# ASIC.net
KiCad netlist of a schematic drawn in Altium Designer
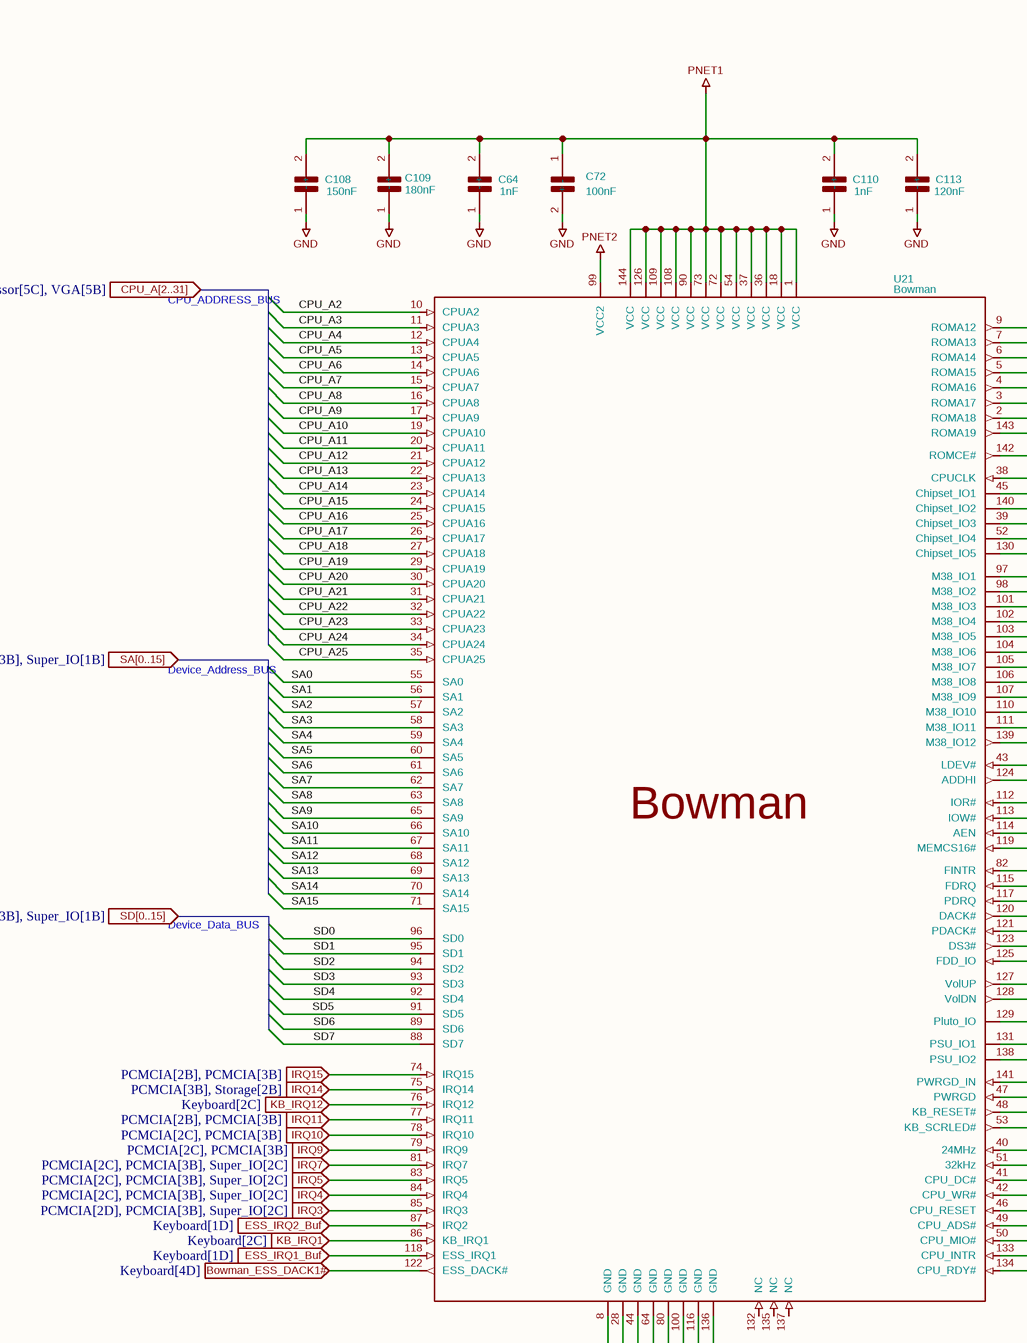
[diagram p0: ASIC.SchDoc, top left]
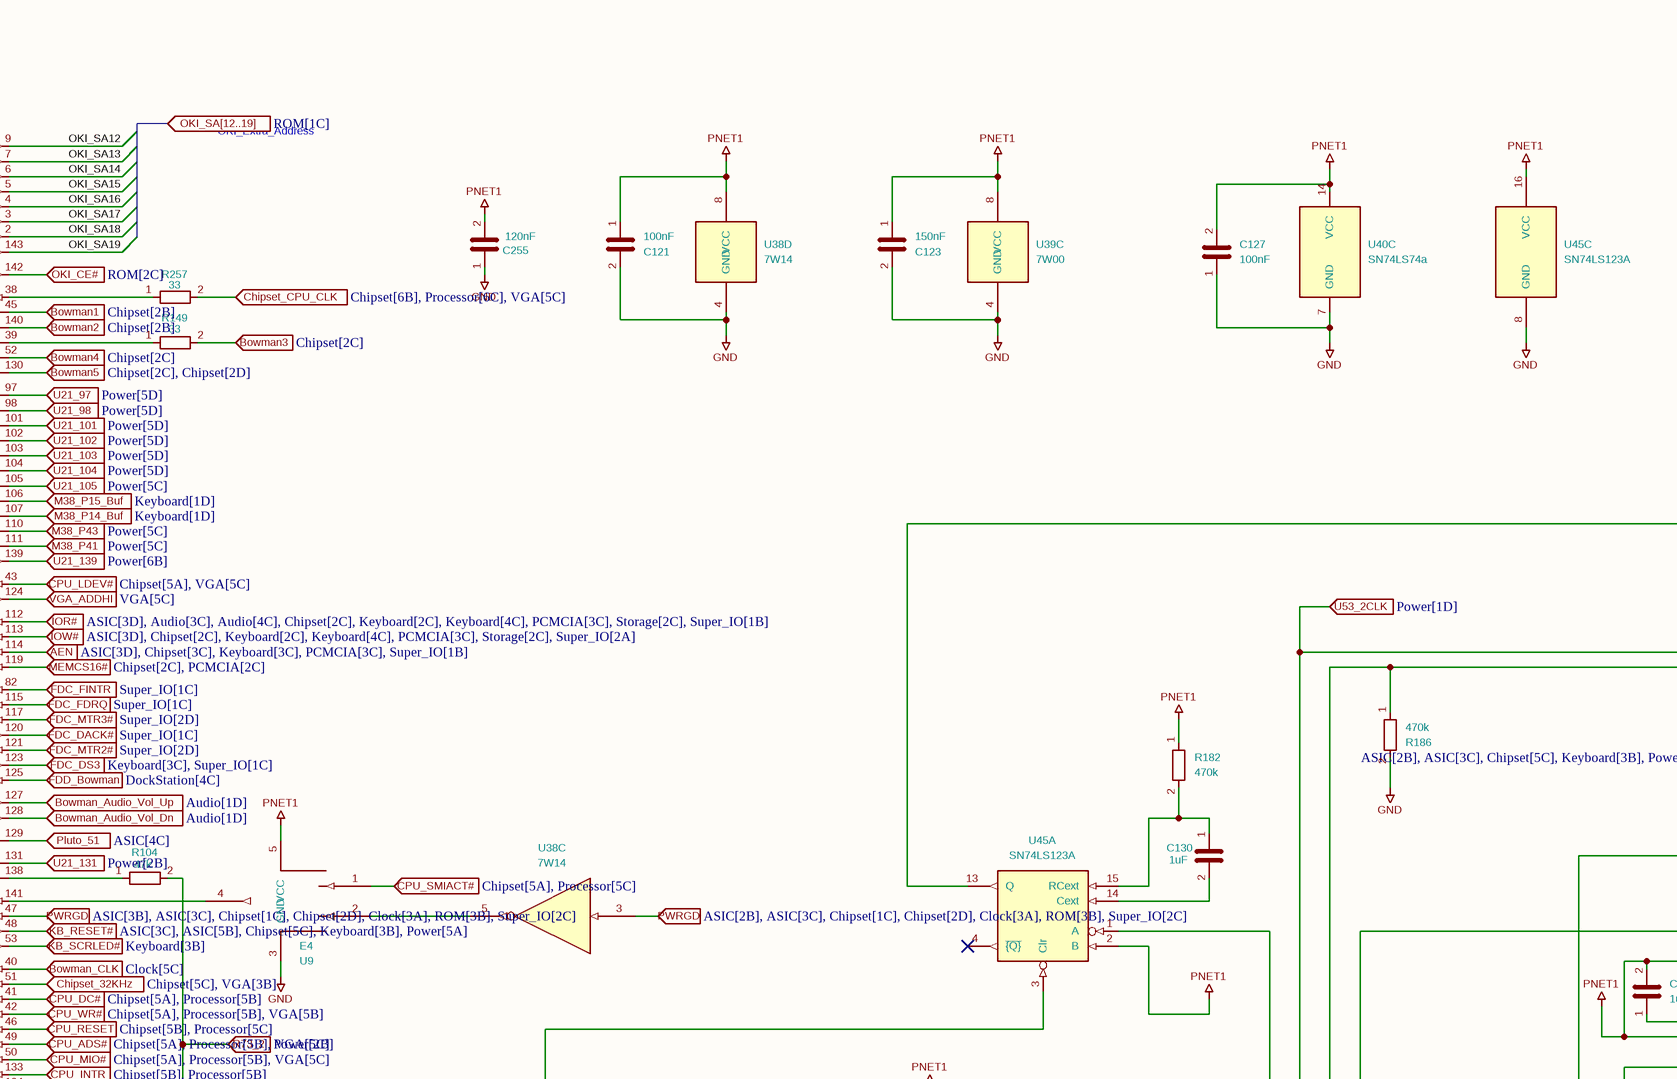
[diagram p1: ASIC.SchDoc, top middle]
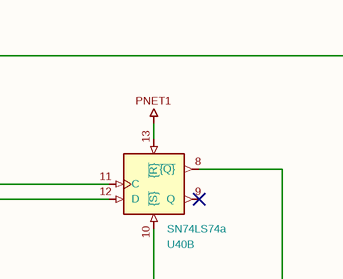
[diagram p2: ASIC.SchDoc, top right]
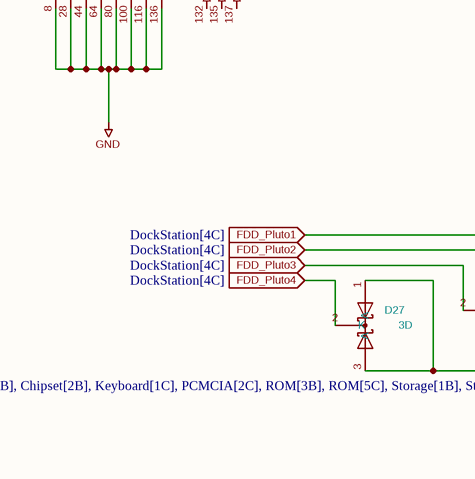
[diagram p3: ASIC.SchDoc, bottom left]
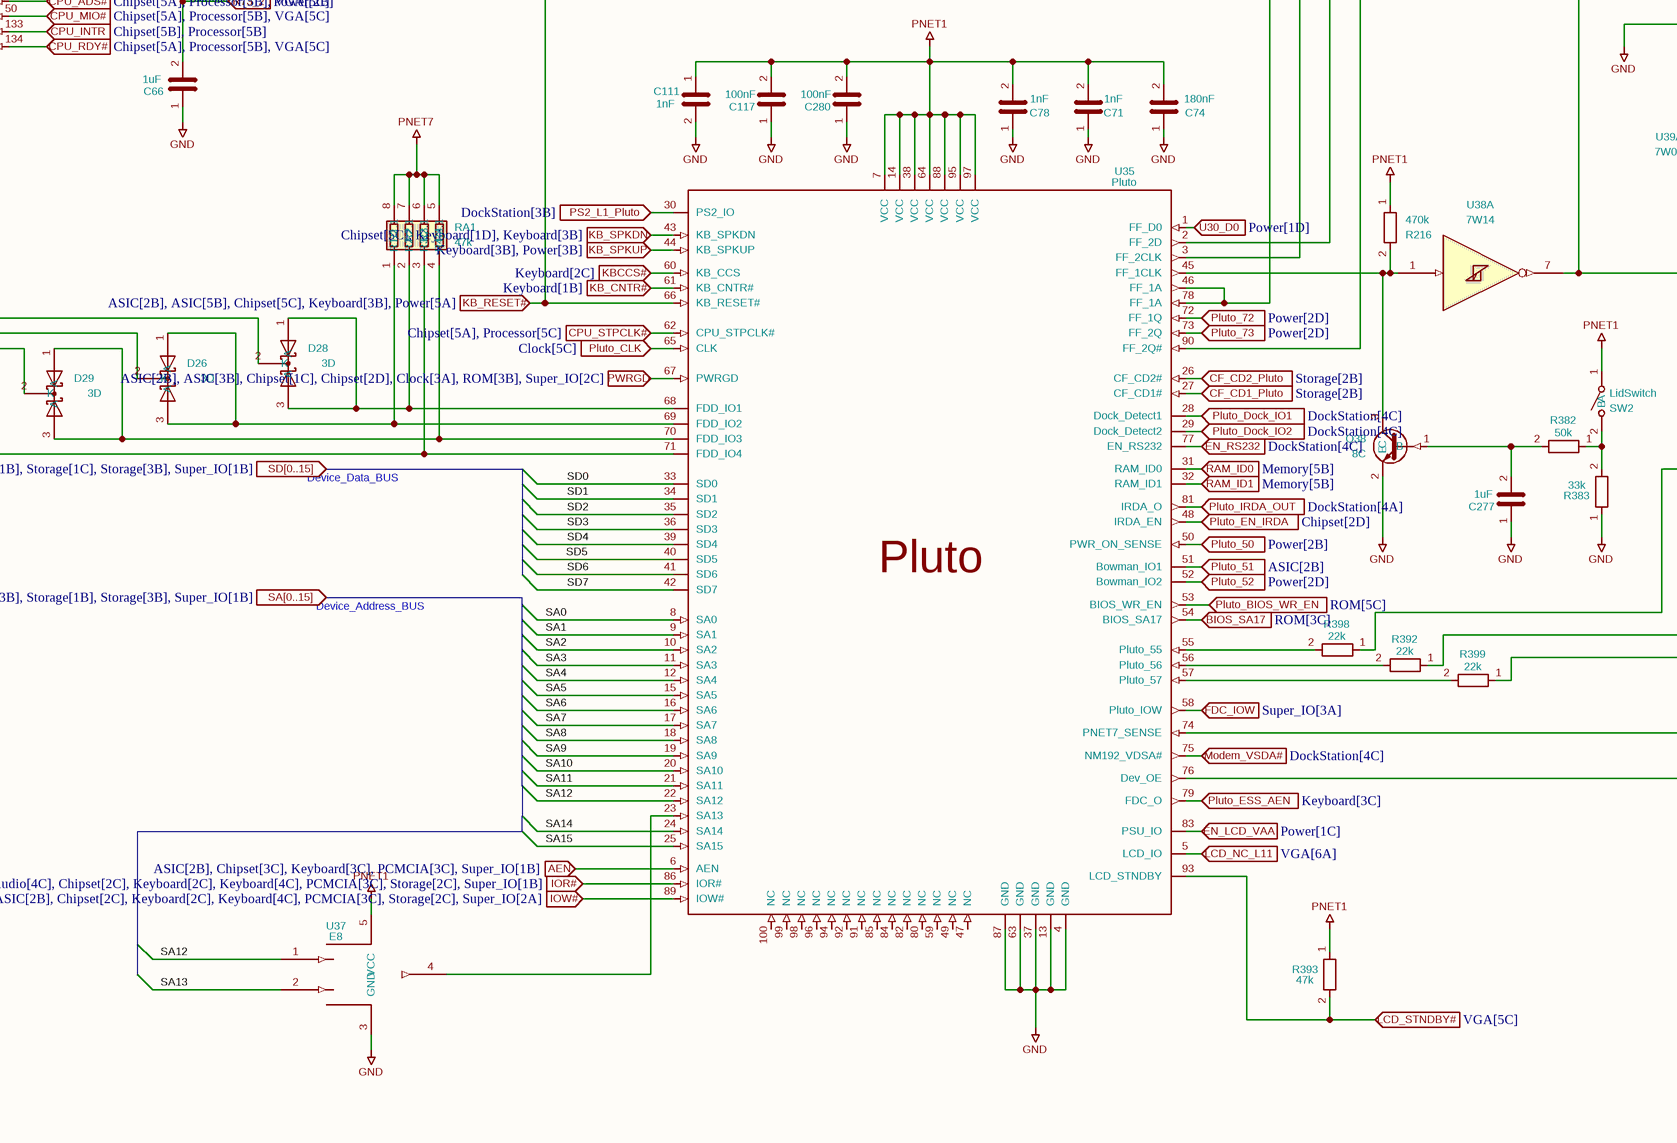
[diagram p4: ASIC.SchDoc, bottom middle]
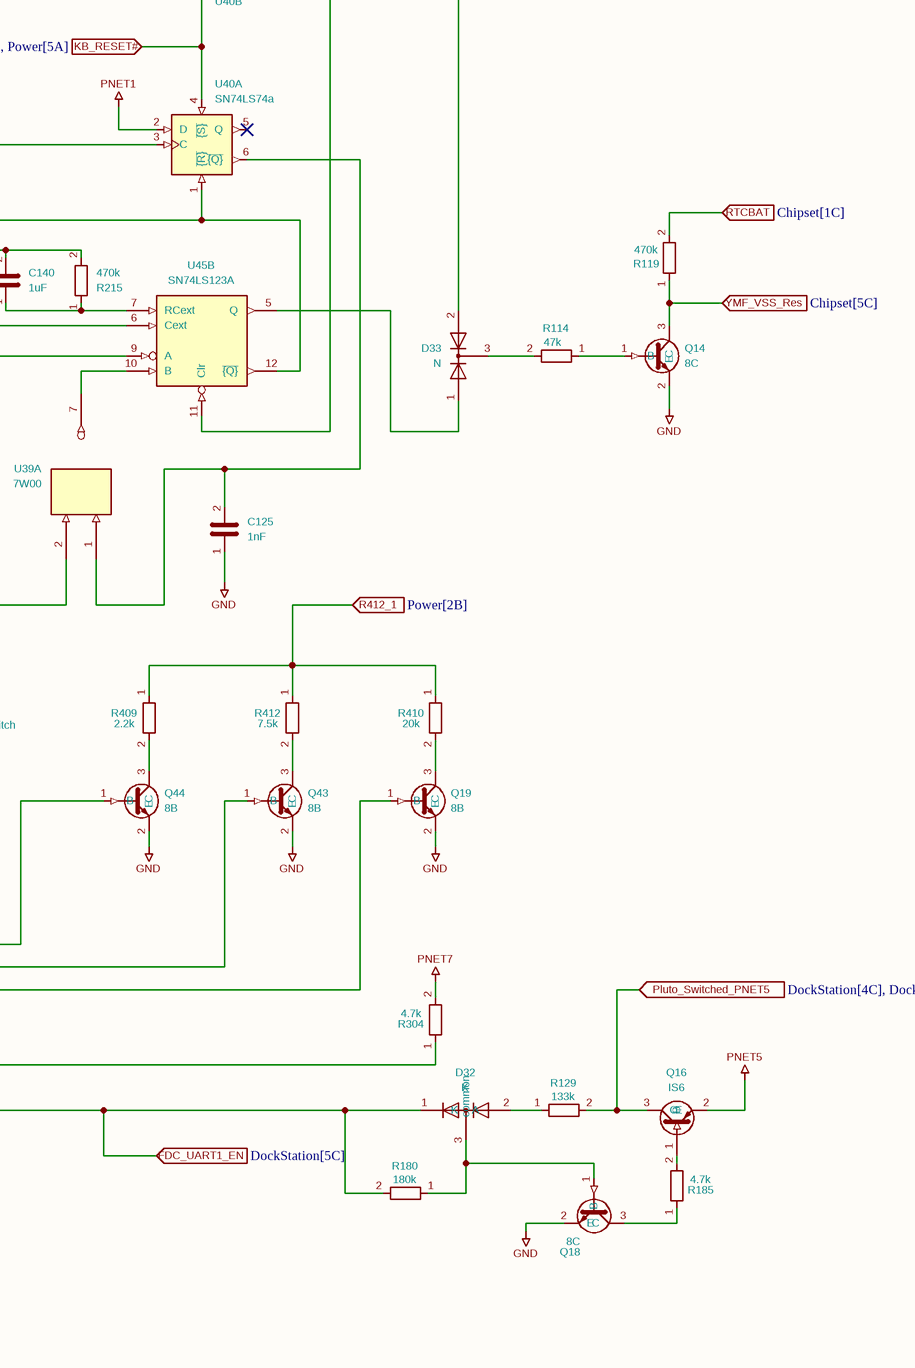
[diagram p5: ASIC.SchDoc, bottom right]

(export (version "E")
  (design (tool "Eeschema 10.0.6"))
  (components
    (comp (ref "C64") (value "1nF") (footprint "C_0402_1005Metric") (libsource (lib "") (part "C_1")))
    (comp (ref "C66") (value "1uF") (footprint "C_0603_1608Metric") (libsource (lib "Device") (part "C")))
    (comp (ref "C71") (value "1nF") (footprint "C_0402_1005Metric") (libsource (lib "Device") (part "C")))
    (comp (ref "C72")
      (value "100nF")
      (footprint "C_0402_1005Metric")
      (libsource (lib "PCM_Elektuur") (part "C"))
    )
    (comp (ref "C74") (value "180nF") (footprint "C_0402_1005Metric") (libsource (lib "Device") (part "C")))
    (comp (ref "C78") (value "1nF") (footprint "C_0402_1005Metric") (libsource (lib "Device") (part "C")))
    (comp (ref "C108") (value "150nF") (footprint "C_0402_1005Metric") (libsource (lib "") (part "C_1")))
    (comp (ref "C109") (value "180nF") (footprint "C_0402_1005Metric") (libsource (lib "") (part "C_1")))
    (comp (ref "C110") (value "1nF") (footprint "C_0402_1005Metric") (libsource (lib "") (part "C_1")))
    (comp (ref "C111") (value "1nF") (footprint "C_0402_1005Metric") (libsource (lib "Device") (part "C")))
    (comp (ref "C113") (value "120nF") (footprint "C_0402_1005Metric") (libsource (lib "") (part "C_1")))
    (comp (ref "C117") (value "100nF") (footprint "C_0402_1005Metric") (libsource (lib "Device") (part "C")))
    (comp (ref "C121") (value "100nF") (footprint "C_0402_1005Metric") (libsource (lib "Device") (part "C")))
    (comp (ref "C123") (value "150nF") (footprint "C_0402_1005Metric") (libsource (lib "Device") (part "C")))
    (comp (ref "C125") (value "1nF") (footprint "C_0402_1005Metric") (libsource (lib "Device") (part "C")))
    (comp (ref "C127") (value "100nF") (footprint "C_0402_1005Metric") (libsource (lib "Device") (part "C")))
    (comp (ref "C130") (value "1uF") (footprint "C_0603_1608Metric") (libsource (lib "Device") (part "C")))
    (comp (ref "C140") (value "1uF") (footprint "C_0603_1608Metric") (libsource (lib "Device") (part "C")))
    (comp (ref "C255") (value "120nF") (footprint "C_0402_1005Metric") (libsource (lib "Device") (part "C")))
    (comp (ref "C277") (value "1uF") (footprint "C_0603_1608Metric") (libsource (lib "Device") (part "C")))
    (comp (ref "C280") (value "100nF") (footprint "C_0402_1005Metric") (libsource (lib "Device") (part "C")))
    (comp (ref "D26")
      (value "3D")
      (footprint "3D")
      (libsource (lib "Device") (part "D_Schottky_Dual_CommonCathode_AKA"))
    )
    (comp (ref "D27")
      (value "3D")
      (footprint "3D")
      (libsource (lib "Device") (part "D_Schottky_Dual_CommonCathode_AKA"))
    )
    (comp (ref "D28")
      (value "3D")
      (footprint "3D")
      (libsource (lib "Device") (part "D_Schottky_Dual_CommonCathode_AKA"))
    )
    (comp (ref "D29")
      (value "3D")
      (footprint "3D")
      (libsource (lib "Device") (part "D_Schottky_Dual_CommonCathode_AKA"))
    )
    (comp (ref "D32")
      (value "K")
      (footprint "SOT-416L")
      (libsource (lib "Device") (part "D_Dual_Series_KAC"))
    )
    (comp (ref "D33") (value "N") (footprint "SOT-416") (libsource (lib "PC110") (part "3D_Diode")))
    (comp (ref "Q14") (value "8C") (footprint "SOT-416") (libsource (lib "Transistor_BJT") (part "MMBTA44")))
    (comp (ref "Q16")
      (value "IS6")
      (footprint "TSOT-23")
      (libsource (lib "PCM_Transistor_BJT_AKL") (part "Q_PNP_Generic_BEC"))
    )
    (comp (ref "Q18") (value "8C") (footprint "SOT-416") (libsource (lib "Transistor_BJT") (part "MMBTA44")))
    (comp (ref "Q19") (value "8B") (footprint "SOT-416") (libsource (lib "Transistor_BJT") (part "MMBTA44")))
    (comp (ref "Q38") (value "8C") (footprint "SOT-416") (libsource (lib "Transistor_BJT") (part "MMBTA44")))
    (comp (ref "Q43") (value "8B") (footprint "SOT-523") (libsource (lib "Transistor_BJT") (part "MMBTA44")))
    (comp (ref "Q44") (value "8B") (footprint "SOT-523") (libsource (lib "Transistor_BJT") (part "MMBTA44")))
    (comp (ref "R104") (value "47k") (footprint "R_0402_1005Metric") (libsource (lib "") (part "R_1")))
    (comp (ref "R114") (value "47k") (footprint "R_0402_1005Metric") (libsource (lib "") (part "R_2")))
    (comp (ref "R119") (value "470k") (footprint "R_0402_1005Metric") (libsource (lib "") (part "R_1")))
    (comp (ref "R129") (value "133k") (footprint "R_0402_1005Metric") (libsource (lib "") (part "R_3")))
    (comp (ref "R149") (value "33") (footprint "R_0402_1005Metric") (libsource (lib "") (part "R_1")))
    (comp (ref "R180") (value "180k") (footprint "R_0402_1005Metric") (libsource (lib "") (part "R_2")))
    (comp (ref "R182") (value "470k") (footprint "R_0402_1005Metric") (libsource (lib "Device") (part "R")))
    (comp (ref "R185") (value "4.7k") (footprint "R_0402_1005Metric") (libsource (lib "") (part "R_3")))
    (comp (ref "R186") (value "470k") (footprint "R_0402_1005Metric") (libsource (lib "") (part "R_2")))
    (comp (ref "R215") (value "470k") (footprint "R_0402_1005Metric") (libsource (lib "") (part "R_1")))
    (comp (ref "R216") (value "470k") (footprint "R_0402_1005Metric") (libsource (lib "") (part "R_2")))
    (comp (ref "R257") (value "33") (footprint "R_0402_1005Metric") (libsource (lib "") (part "R_1")))
    (comp (ref "R304") (value "4.7k") (footprint "R_0402_1005Metric") (libsource (lib "") (part "R_1")))
    (comp (ref "R382") (value "50k") (footprint "R_0402_1005Metric") (libsource (lib "") (part "R_2")))
    (comp (ref "R383") (value "33k") (footprint "R_0402_1005Metric") (libsource (lib "") (part "R_1")))
    (comp (ref "R392") (value "22k") (footprint "R_0402_1005Metric") (libsource (lib "") (part "R_2")))
    (comp (ref "R393") (value "47k") (footprint "R_0402_1005Metric") (libsource (lib "Device") (part "R")))
    (comp (ref "R398") (value "22k") (footprint "R_0402_1005Metric") (libsource (lib "") (part "R_2")))
    (comp (ref "R399") (value "22k") (footprint "R_0402_1005Metric") (libsource (lib "") (part "R_2")))
    (comp (ref "R409") (value "2.2k") (footprint "R_0402_1005Metric") (libsource (lib "Device") (part "R")))
    (comp (ref "R410") (value "20k") (footprint "R_0402_1005Metric") (libsource (lib "Device") (part "R")))
    (comp (ref "R412") (value "7.5k") (footprint "R_0402_1005Metric") (libsource (lib "Device") (part "R")))
    (comp (ref "RA1") (value "47k") (footprint "R-array") (libsource (lib "Device") (part "R_Pack04")))
    (comp (ref "SW2") (value "LidSwitch") (footprint "LidSwitch") (libsource (lib "Switch") (part "SW_SPST")))
    (comp (ref "U9") (value "E4") (footprint "SOT-353") (libsource (lib "74xGxx") (part "74AHC1G32")))
    (comp (ref "U21") (value "Bowman") (footprint "Bowman") (libsource (lib "PC110") (part "Bowman")))
    (comp (ref "U35") (value "Pluto") (footprint "Pluto") (libsource (lib "PC110") (part "Pluto")))
    (comp (ref "U37") (value "E8") (footprint "SOT-353") (libsource (lib "74xGxx") (part "74AHC1G86")))
    (comp (ref "U38") (value "7W14") (footprint "sso-8") (libsource (lib "") (part "74LVC3G14_1")))
    (comp (ref "U39") (value "7W00") (footprint "sso-8") (libsource (lib "74xGxx") (part "74AHC2G00")))
    (comp (ref "U40")
      (value "SN74LS74a")
      (footprint "TSSOP-14_4.4x5mm_P0.65mm")
      (libsource (lib "74xx") (part "74HC74"))
    )
    (comp (ref "U45")
      (value "SN74LS123A")
      (footprint "TSSOP-16_4.4x5mm_P0.65mm")
      (libsource (lib "74xx") (part "74HC123"))
    )
  )
  (nets
    (net (code "15") (name "/AEN") (class "Default")
      (node (ref "U21") (pin "114") (pinfunction "AEN_114") (pintype "input"))
      (node (ref "U35") (pin "6") (pinfunction "AEN_6") (pintype "input"))
    )
    (net (code "16") (name "/BIOS_SA17") (class "Default")
      (node (ref "U35") (pin "54") (pinfunction "BIOS_SA17_54") (pintype "output"))
    )
    (net (code "17") (name "/Bowman1") (class "Default")
      (node (ref "U21") (pin "45") (pinfunction "Chipset_IO1_45") (pintype "bidirectional"))
    )
    (net (code "18") (name "/Bowman2") (class "Default")
      (node (ref "U21") (pin "140") (pinfunction "Chipset_IO2_140") (pintype "bidirectional"))
    )
    (net (code "19") (name "/Bowman3") (class "Default")
      (node (ref "R149") (pin "2") (pinfunction "2_2") (pintype "passive"))
    )
    (net (code "20") (name "/Bowman4") (class "Default")
      (node (ref "U21") (pin "52") (pinfunction "Chipset_IO4_52") (pintype "bidirectional"))
    )
    (net (code "21") (name "/Bowman5") (class "Default")
      (node (ref "U21") (pin "130") (pinfunction "Chipset_IO5_130") (pintype "bidirectional"))
    )
    (net (code "22") (name "/Bowman_Audio_Vol_Dn") (class "Default")
      (node (ref "U21") (pin "128") (pinfunction "VolDN_128") (pintype "output"))
    )
    (net (code "23") (name "/Bowman_Audio_Vol_Up") (class "Default")
      (node (ref "U21") (pin "127") (pinfunction "VolUP_127") (pintype "output"))
    )
    (net (code "24") (name "/Bowman_CLK") (class "Default")
      (node (ref "U21") (pin "40") (pinfunction "24MHz_40") (pintype "input"))
    )
    (net (code "25") (name "/Bowman_ESS_DACK1#") (class "Default")
      (node (ref "U21") (pin "122") (pinfunction "ESS_DACK#_122") (pintype "output"))
    )
    (net (code "26") (name "/CF_CD1_Pluto") (class "Default")
      (node (ref "U35") (pin "27") (pinfunction "CF_CD1#_27") (pintype "input"))
    )
    (net (code "27") (name "/CF_CD2_Pluto") (class "Default")
      (node (ref "U35") (pin "26") (pinfunction "CF_CD2#_26") (pintype "input"))
    )
    (net (code "28") (name "/CPU_A2") (class "Default")
      (node (ref "U21") (pin "10") (pinfunction "CPUA2_10") (pintype "input"))
    )
    (net (code "29") (name "/CPU_A3") (class "Default")
      (node (ref "U21") (pin "11") (pinfunction "CPUA3_11") (pintype "input"))
    )
    (net (code "30") (name "/CPU_A4") (class "Default")
      (node (ref "U21") (pin "12") (pinfunction "CPUA4_12") (pintype "input"))
    )
    (net (code "31") (name "/CPU_A5") (class "Default")
      (node (ref "U21") (pin "13") (pinfunction "CPUA5_13") (pintype "input"))
    )
    (net (code "32") (name "/CPU_A6") (class "Default")
      (node (ref "U21") (pin "14") (pinfunction "CPUA6_14") (pintype "input"))
    )
    (net (code "33") (name "/CPU_A7") (class "Default")
      (node (ref "U21") (pin "15") (pinfunction "CPUA7_15") (pintype "input"))
    )
    (net (code "34") (name "/CPU_A8") (class "Default")
      (node (ref "U21") (pin "16") (pinfunction "CPUA8_16") (pintype "input"))
    )
    (net (code "35") (name "/CPU_A9") (class "Default")
      (node (ref "U21") (pin "17") (pinfunction "CPUA9_17") (pintype "input"))
    )
    (net (code "36") (name "/CPU_A10") (class "Default")
      (node (ref "U21") (pin "19") (pinfunction "CPUA10_19") (pintype "input"))
    )
    (net (code "37") (name "/CPU_A11") (class "Default")
      (node (ref "U21") (pin "20") (pinfunction "CPUA11_20") (pintype "input"))
    )
    (net (code "38") (name "/CPU_A12") (class "Default")
      (node (ref "U21") (pin "21") (pinfunction "CPUA12_21") (pintype "input"))
    )
    (net (code "39") (name "/CPU_A13") (class "Default")
      (node (ref "U21") (pin "22") (pinfunction "CPUA13_22") (pintype "input"))
    )
    (net (code "40") (name "/CPU_A14") (class "Default")
      (node (ref "U21") (pin "23") (pinfunction "CPUA14_23") (pintype "input"))
    )
    (net (code "41") (name "/CPU_A15") (class "Default")
      (node (ref "U21") (pin "24") (pinfunction "CPUA15_24") (pintype "input"))
    )
    (net (code "42") (name "/CPU_A16") (class "Default")
      (node (ref "U21") (pin "25") (pinfunction "CPUA16_25") (pintype "input"))
    )
    (net (code "43") (name "/CPU_A17") (class "Default")
      (node (ref "U21") (pin "26") (pinfunction "CPUA17_26") (pintype "input"))
    )
    (net (code "44") (name "/CPU_A18") (class "Default")
      (node (ref "U21") (pin "27") (pinfunction "CPUA18_27") (pintype "input"))
    )
    (net (code "45") (name "/CPU_A19") (class "Default")
      (node (ref "U21") (pin "29") (pinfunction "CPUA19_29") (pintype "input"))
    )
    (net (code "46") (name "/CPU_A20") (class "Default")
      (node (ref "U21") (pin "30") (pinfunction "CPUA20_30") (pintype "input"))
    )
    (net (code "47") (name "/CPU_A21") (class "Default")
      (node (ref "U21") (pin "31") (pinfunction "CPUA21_31") (pintype "input"))
    )
    (net (code "48") (name "/CPU_A22") (class "Default")
      (node (ref "U21") (pin "32") (pinfunction "CPUA22_32") (pintype "input"))
    )
    (net (code "49") (name "/CPU_A23") (class "Default")
      (node (ref "U21") (pin "33") (pinfunction "CPUA23_33") (pintype "input"))
    )
    (net (code "50") (name "/CPU_A24") (class "Default")
      (node (ref "U21") (pin "34") (pinfunction "CPUA24_34") (pintype "input"))
    )
    (net (code "51") (name "/CPU_A25") (class "Default")
      (node (ref "U21") (pin "35") (pinfunction "CPUA25_35") (pintype "input"))
    )
    (net (code "52") (name "/CPU_ADS#") (class "Default")
      (node (ref "U21") (pin "49") (pinfunction "CPU_ADS#_49") (pintype "input"))
    )
    (net (code "54") (name "/CPU_DC#") (class "Default")
      (node (ref "U21") (pin "41") (pinfunction "CPU_DC#_41") (pintype "input"))
    )
    (net (code "55") (name "/CPU_INTR") (class "Default")
      (node (ref "U21") (pin "133") (pinfunction "CPU_INTR_133") (pintype "input"))
    )
    (net (code "56") (name "/CPU_LDEV#") (class "Default")
      (node (ref "U21") (pin "43") (pinfunction "LDEV#_43") (pintype "input"))
    )
    (net (code "57") (name "/CPU_MIO#") (class "Default")
      (node (ref "U21") (pin "50") (pinfunction "CPU_MIO#_50") (pintype "input"))
    )
    (net (code "58") (name "/CPU_RDY#") (class "Default")
      (node (ref "U21") (pin "134") (pinfunction "CPU_RDY#_134") (pintype "input"))
    )
    (net (code "59") (name "/CPU_RESET") (class "Default")
      (node (ref "U21") (pin "46") (pinfunction "CPU_RESET_46") (pintype "input"))
    )
    (net (code "60") (name "/CPU_SMIACT#") (class "Default")
      (node (ref "U9") (pin "1") (pinfunction "1_1") (pintype "input"))
    )
    (net (code "61") (name "/CPU_STPCLK#") (class "Default")
      (node (ref "U35") (pin "62") (pinfunction "CPU_STPCLK#_62") (pintype "input"))
    )
    (net (code "62") (name "/CPU_WR#") (class "Default")
      (node (ref "U21") (pin "42") (pinfunction "CPU_WR#_42") (pintype "input"))
    )
    (net (code "63") (name "/Chipset_32KHz") (class "Default")
      (node (ref "U21") (pin "51") (pinfunction "32kHz_51") (pintype "input"))
    )
    (net (code "64") (name "/Chipset_CPU_CLK") (class "Default")
      (node (ref "R257") (pin "2") (pinfunction "2_2") (pintype "passive"))
    )
    (net (code "65") (name "/EN_LCD_VAA") (class "Default")
      (node (ref "U35") (pin "83") (pinfunction "PSU_IO_83") (pintype "bidirectional"))
    )
    (net (code "66") (name "/EN_RS232") (class "Default")
      (node (ref "U35") (pin "77") (pinfunction "EN_RS232_77") (pintype "bidirectional"))
    )
    (net (code "67") (name "/ESS_IRQ1_Buf") (class "Default")
      (node (ref "U21") (pin "118") (pinfunction "ESS_IRQ1_118") (pintype "input"))
    )
    (net (code "68") (name "/ESS_IRQ2_Buf") (class "Default")
      (node (ref "U21") (pin "87") (pinfunction "IRQ2_87") (pintype "input"))
    )
    (net (code "69") (name "/FDC_DACK#") (class "Default")
      (node (ref "U21") (pin "120") (pinfunction "DACK#_120") (pintype "output"))
    )
    (net (code "70") (name "/FDC_DS3") (class "Default")
      (node (ref "U21") (pin "123") (pinfunction "DS3#_123") (pintype "output"))
    )
    (net (code "71") (name "/FDC_FDRQ") (class "Default")
      (node (ref "U21") (pin "115") (pinfunction "FDRQ_115") (pintype "input"))
    )
    (net (code "72") (name "/FDC_FINTR") (class "Default")
      (node (ref "U21") (pin "82") (pinfunction "FINTR_82") (pintype "input"))
    )
    (net (code "73") (name "/FDC_IOW") (class "Default")
      (node (ref "U35") (pin "58") (pinfunction "Pluto_IOW_58") (pintype "output"))
    )
    (net (code "74") (name "/FDC_MTR2#") (class "Default")
      (node (ref "U21") (pin "121") (pinfunction "PDACK#_121") (pintype "input"))
    )
    (net (code "75") (name "/FDC_MTR3#") (class "Default")
      (node (ref "U21") (pin "117") (pinfunction "PDRQ_117") (pintype "input"))
    )
    (net (code "76") (name "/FDC_UART1_EN") (class "Default")
      (node (ref "D32") (pin "1") (pinfunction "K_1") (pintype "passive"))
      (node (ref "R180") (pin "2") (pinfunction "2_2") (pintype "passive"))
      (node (ref "U35") (pin "76") (pinfunction "Dev_OE_76") (pintype "output"))
    )
    (net (code "77") (name "/FDD_Bowman") (class "Default")
      (node (ref "U21") (pin "125") (pinfunction "FDD_IO_125") (pintype "input"))
    )
    (net (code "78") (name "/FDD_Pluto1") (class "Default")
      (node (ref "D28") (pin "2") (pinfunction "K_2") (pintype "passive"))
    )
    (net (code "79") (name "/FDD_Pluto2") (class "Default")
      (node (ref "D26") (pin "2") (pinfunction "K_2") (pintype "passive"))
    )
    (net (code "80") (name "/FDD_Pluto3") (class "Default")
      (node (ref "D29") (pin "2") (pinfunction "K_2") (pintype "passive"))
    )
    (net (code "81") (name "/FDD_Pluto4") (class "Default")
      (node (ref "D27") (pin "2") (pinfunction "K_2") (pintype "passive"))
    )
    (net (code "82") (name "/IOR#") (class "Default")
      (node (ref "U21") (pin "112") (pinfunction "IOR#_112") (pintype "input"))
      (node (ref "U35") (pin "86") (pinfunction "IOR#_86") (pintype "input"))
    )
    (net (code "83") (name "/IOW#") (class "Default")
      (node (ref "U21") (pin "113") (pinfunction "IOW#_113") (pintype "input"))
      (node (ref "U35") (pin "89") (pinfunction "IOW#_89") (pintype "input"))
    )
    (net (code "84") (name "/IRQ3") (class "Default")
      (node (ref "U21") (pin "85") (pinfunction "IRQ3_85") (pintype "input"))
    )
    (net (code "85") (name "/IRQ4") (class "Default")
      (node (ref "U21") (pin "84") (pinfunction "IRQ4_84") (pintype "input"))
    )
    (net (code "86") (name "/IRQ5") (class "Default")
      (node (ref "U21") (pin "83") (pinfunction "IRQ5_83") (pintype "input"))
    )
    (net (code "87") (name "/IRQ7") (class "Default")
      (node (ref "U21") (pin "81") (pinfunction "IRQ7_81") (pintype "input"))
    )
    (net (code "88") (name "/IRQ9") (class "Default")
      (node (ref "U21") (pin "79") (pinfunction "IRQ9_79") (pintype "input"))
    )
    (net (code "89") (name "/IRQ10") (class "Default")
      (node (ref "U21") (pin "78") (pinfunction "IRQ10_78") (pintype "input"))
    )
    (net (code "90") (name "/IRQ11") (class "Default")
      (node (ref "U21") (pin "77") (pinfunction "IRQ11_77") (pintype "input"))
    )
    (net (code "91") (name "/IRQ14") (class "Default")
      (node (ref "U21") (pin "75") (pinfunction "IRQ14_75") (pintype "input"))
    )
    (net (code "92") (name "/IRQ15") (class "Default")
      (node (ref "U21") (pin "74") (pinfunction "IRQ15_74") (pintype "input"))
    )
    (net (code "93") (name "/KBCCS#") (class "Default")
      (node (ref "U35") (pin "60") (pinfunction "KB_CCS_60") (pintype "input"))
    )
    (net (code "94") (name "/KB_CNTR#") (class "Default")
      (node (ref "U35") (pin "61") (pinfunction "KB_CNTR#_61") (pintype "input"))
    )
    (net (code "95") (name "/KB_IRQ1") (class "Default")
      (node (ref "U21") (pin "86") (pinfunction "KB_IRQ1_86") (pintype "input"))
    )
    (net (code "96") (name "/KB_IRQ12") (class "Default")
      (node (ref "U21") (pin "76") (pinfunction "IRQ12_76") (pintype "input"))
    )
    (net (code "97") (name "/KB_RESET#") (class "Default")
      (node (ref "U21") (pin "48") (pinfunction "KB_RESET#_48") (pintype "output"))
      (node (ref "U35") (pin "66") (pinfunction "KB_RESET#_66") (pintype "input"))
      (node (ref "U40") (pin "10") (pinfunction "~{{S}}_10") (pintype "input"))
      (node (ref "U40") (pin "4") (pinfunction "~{{S}}_4") (pintype "input"))
      (node (ref "U45") (pin "3") (pinfunction "Clr_3") (pintype "input"))
    )
    (net (code "98") (name "/KB_SCRLED#") (class "Default")
      (node (ref "U21") (pin "53") (pinfunction "KB_SCRLED#_53") (pintype "output"))
    )
    (net (code "99") (name "/KB_SPKDN") (class "Default")
      (node (ref "U35") (pin "43") (pinfunction "KB_SPKDN_43") (pintype "input"))
    )
    (net (code "100") (name "/KB_SPKUP") (class "Default")
      (node (ref "U35") (pin "44") (pinfunction "KB_SPKUP_44") (pintype "input"))
    )
    (net (code "101") (name "/LCD_NC_L11") (class "Default")
      (node (ref "U35") (pin "5") (pinfunction "LCD_IO_5") (pintype "bidirectional"))
    )
    (net (code "102") (name "/LCD_STNDBY#") (class "Default")
      (node (ref "R393") (pin "2") (pinfunction "2_2") (pintype "passive"))
      (node (ref "U35") (pin "93") (pinfunction "LCD_STNDBY_93") (pintype "bidirectional"))
    )
    (net (code "103") (name "/M38_P14_Buf") (class "Default")
      (node (ref "U21") (pin "107") (pinfunction "M38_IO9_107") (pintype "bidirectional"))
    )
    (net (code "104") (name "/M38_P15_Buf") (class "Default")
      (node (ref "U21") (pin "106") (pinfunction "M38_IO8_106") (pintype "bidirectional"))
    )
    (net (code "105") (name "/M38_P41") (class "Default")
      (node (ref "U21") (pin "111") (pinfunction "M38_IO11_111") (pintype "bidirectional"))
    )
    (net (code "106") (name "/M38_P43") (class "Default")
      (node (ref "U21") (pin "110") (pinfunction "M38_IO10_110") (pintype "bidirectional"))
    )
    (net (code "107") (name "/MEMCS16#") (class "Default")
      (node (ref "U21") (pin "119") (pinfunction "MEMCS16#_119") (pintype "input"))
    )
    (net (code "108") (name "/Modem_VSDA#") (class "Default")
      (node (ref "U35") (pin "75") (pinfunction "NM192_VDSA#_75") (pintype "output"))
    )
    (net (code "109") (name "/OKI_CE#") (class "Default")
      (node (ref "U21") (pin "142") (pinfunction "ROMCE#_142") (pintype "output"))
    )
    (net (code "110") (name "/OKI_SA12") (class "Default")
      (node (ref "U21") (pin "9") (pinfunction "ROMA12_9") (pintype "output"))
    )
    (net (code "111") (name "/OKI_SA13") (class "Default")
      (node (ref "U21") (pin "7") (pinfunction "ROMA13_7") (pintype "output"))
    )
    (net (code "112") (name "/OKI_SA14") (class "Default")
      (node (ref "U21") (pin "6") (pinfunction "ROMA14_6") (pintype "output"))
    )
    (net (code "113") (name "/OKI_SA15") (class "Default")
      (node (ref "U21") (pin "5") (pinfunction "ROMA15_5") (pintype "output"))
    )
    (net (code "114") (name "/OKI_SA16") (class "Default")
      (node (ref "U21") (pin "4") (pinfunction "ROMA16_4") (pintype "output"))
    )
    (net (code "115") (name "/OKI_SA17") (class "Default")
      (node (ref "U21") (pin "3") (pinfunction "ROMA17_3") (pintype "output"))
    )
    (net (code "116") (name "/OKI_SA18") (class "Default")
      (node (ref "U21") (pin "2") (pinfunction "ROMA18_2") (pintype "output"))
    )
    (net (code "117") (name "/OKI_SA19") (class "Default")
      (node (ref "U21") (pin "143") (pinfunction "ROMA19_143") (pintype "output"))
    )
    (net (code "119") (name "/PS2_L1_Pluto") (class "Default")
      (node (ref "U35") (pin "30") (pinfunction "PS2_IO_30") (pintype "bidirectional"))
    )
    (net (code "120") (name "/PWRGD") (class "Default")
      (node (ref "U21") (pin "47") (pinfunction "PWRGD_47") (pintype "input"))
      (node (ref "U35") (pin "67") (pinfunction "PWRGD_67") (pintype "input"))
      (node (ref "U38") (pin "3") (pinfunction "3_3") (pintype "input"))
    )
    (net (code "121") (name "/Pluto_50") (class "Default")
      (node (ref "U35") (pin "50") (pinfunction "PWR_ON_SENSE_50") (pintype "input"))
    )
    (net (code "122") (name "/Pluto_51") (class "Default")
      (node (ref "U21") (pin "129") (pinfunction "Pluto_IO_129") (pintype "bidirectional"))
      (node (ref "U35") (pin "51") (pinfunction "Bowman_IO1_51") (pintype "bidirectional"))
    )
    (net (code "123") (name "/Pluto_52") (class "Default")
      (node (ref "U35") (pin "52") (pinfunction "Bowman_IO2_52") (pintype "bidirectional"))
    )
    (net (code "124") (name "/Pluto_72") (class "Default")
      (node (ref "U35") (pin "72") (pinfunction "FF_1Q_72") (pintype "input"))
    )
    (net (code "125") (name "/Pluto_73") (class "Default")
      (node (ref "U35") (pin "73") (pinfunction "FF_2Q_73") (pintype "input"))
    )
    (net (code "126") (name "/Pluto_BIOS_WR_EN") (class "Default")
      (node (ref "U35") (pin "53") (pinfunction "BIOS_WR_EN_53") (pintype "output"))
    )
    (net (code "127") (name "/Pluto_CLK") (class "Default")
      (node (ref "U35") (pin "65") (pinfunction "CLK_65") (pintype "input"))
    )
    (net (code "128") (name "/Pluto_Dock_IO1") (class "Default")
      (node (ref "U35") (pin "28") (pinfunction "Dock_Detect1_28") (pintype "bidirectional"))
    )
    (net (code "129") (name "/Pluto_Dock_IO2") (class "Default")
      (node (ref "U35") (pin "29") (pinfunction "Dock_Detect2_29") (pintype "bidirectional"))
    )
    (net (code "130") (name "/Pluto_EN_IRDA") (class "Default")
      (node (ref "U35") (pin "48") (pinfunction "IRDA_EN_48") (pintype "output"))
    )
    (net (code "131") (name "/Pluto_ESS_AEN") (class "Default")
      (node (ref "U35") (pin "79") (pinfunction "FDC_O_79") (pintype "output"))
    )
    (net (code "132") (name "/Pluto_IRDA_OUT") (class "Default")
      (node (ref "U35") (pin "81") (pinfunction "IRDA_O_81") (pintype "output"))
    )
    (net (code "133") (name "/Pluto_Switched_PNET5") (class "Default")
      (node (ref "Q16") (pin "3") (pinfunction "C_3") (pintype "passive"))
      (node (ref "R129") (pin "2") (pinfunction "2_2") (pintype "passive"))
    )
    (net (code "134") (name "/R73_2") (class "Default")
      (node (ref "C66") (pin "2") (pinfunction "2_2") (pintype "passive"))
      (node (ref "R104") (pin "2") (pinfunction "2_2") (pintype "passive"))
    )
    (net (code "135") (name "/R412_1") (class "Default")
      (node (ref "R409") (pin "1") (pinfunction "1_1") (pintype "passive"))
      (node (ref "R410") (pin "1") (pinfunction "1_1") (pintype "passive"))
      (node (ref "R412") (pin "1") (pinfunction "1_1") (pintype "passive"))
    )
    (net (code "136") (name "/RAM_ID0") (class "Default")
      (node (ref "U35") (pin "31") (pinfunction "RAM_ID0_31") (pintype "bidirectional"))
    )
    (net (code "137") (name "/RAM_ID1") (class "Default")
      (node (ref "U35") (pin "32") (pinfunction "RAM_ID1_32") (pintype "bidirectional"))
    )
    (net (code "138") (name "/RTCBAT") (class "Default")
      (node (ref "R119") (pin "2") (pinfunction "2_2") (pintype "passive"))
    )
    (net (code "139") (name "/SA0") (class "Default")
      (node (ref "U21") (pin "55") (pinfunction "SA0_55") (pintype "bidirectional"))
      (node (ref "U35") (pin "8") (pinfunction "SA0_8") (pintype "input"))
    )
    (net (code "140") (name "/SA1") (class "Default")
      (node (ref "U21") (pin "56") (pinfunction "SA1_56") (pintype "bidirectional"))
      (node (ref "U35") (pin "9") (pinfunction "SA1_9") (pintype "input"))
    )
    (net (code "141") (name "/SA2") (class "Default")
      (node (ref "U21") (pin "57") (pinfunction "SA2_57") (pintype "bidirectional"))
      (node (ref "U35") (pin "10") (pinfunction "SA2_10") (pintype "input"))
    )
    (net (code "142") (name "/SA3") (class "Default")
      (node (ref "U21") (pin "58") (pinfunction "SA3_58") (pintype "bidirectional"))
      (node (ref "U35") (pin "11") (pinfunction "SA3_11") (pintype "input"))
    )
    (net (code "143") (name "/SA4") (class "Default")
      (node (ref "U21") (pin "59") (pinfunction "SA4_59") (pintype "bidirectional"))
      (node (ref "U35") (pin "12") (pinfunction "SA4_12") (pintype "input"))
    )
    (net (code "144") (name "/SA5") (class "Default")
      (node (ref "U21") (pin "60") (pinfunction "SA5_60") (pintype "bidirectional"))
      (node (ref "U35") (pin "15") (pinfunction "SA5_15") (pintype "input"))
    )
    (net (code "145") (name "/SA6") (class "Default")
      (node (ref "U21") (pin "61") (pinfunction "SA6_61") (pintype "bidirectional"))
      (node (ref "U35") (pin "16") (pinfunction "SA6_16") (pintype "input"))
    )
    (net (code "146") (name "/SA7") (class "Default")
      (node (ref "U21") (pin "62") (pinfunction "SA7_62") (pintype "bidirectional"))
      (node (ref "U35") (pin "17") (pinfunction "SA7_17") (pintype "input"))
    )
    (net (code "147") (name "/SA8") (class "Default")
      (node (ref "U21") (pin "63") (pinfunction "SA8_63") (pintype "bidirectional"))
      (node (ref "U35") (pin "18") (pinfunction "SA8_18") (pintype "input"))
    )
    (net (code "148") (name "/SA9") (class "Default")
      (node (ref "U21") (pin "65") (pinfunction "SA9_65") (pintype "bidirectional"))
      (node (ref "U35") (pin "19") (pinfunction "SA9_19") (pintype "input"))
    )
    (net (code "149") (name "/SA10") (class "Default")
      (node (ref "U21") (pin "66") (pinfunction "SA10_66") (pintype "bidirectional"))
      (node (ref "U35") (pin "20") (pinfunction "SA10_20") (pintype "input"))
    )
    (net (code "150") (name "/SA11") (class "Default")
      (node (ref "U21") (pin "67") (pinfunction "SA11_67") (pintype "bidirectional"))
      (node (ref "U35") (pin "21") (pinfunction "SA11_21") (pintype "input"))
    )
    (net (code "151") (name "/SA12") (class "Default")
      (node (ref "U21") (pin "68") (pinfunction "SA12_68") (pintype "bidirectional"))
      (node (ref "U35") (pin "22") (pinfunction "SA12_22") (pintype "input"))
      (node (ref "U37") (pin "1") (pinfunction "1_1") (pintype "input"))
    )
    (net (code "152") (name "/SA13") (class "Default")
      (node (ref "U21") (pin "69") (pinfunction "SA13_69") (pintype "bidirectional"))
      (node (ref "U37") (pin "2") (pinfunction "2_2") (pintype "input"))
    )
    (net (code "153") (name "/SA14") (class "Default")
      (node (ref "U21") (pin "70") (pinfunction "SA14_70") (pintype "bidirectional"))
      (node (ref "U35") (pin "24") (pinfunction "SA14_24") (pintype "input"))
    )
    (net (code "154") (name "/SA15") (class "Default")
      (node (ref "U21") (pin "71") (pinfunction "SA15_71") (pintype "bidirectional"))
      (node (ref "U35") (pin "25") (pinfunction "SA15_25") (pintype "input"))
    )
    (net (code "156") (name "/SD0") (class "Default")
      (node (ref "U21") (pin "96") (pinfunction "SD0_96") (pintype "bidirectional"))
      (node (ref "U35") (pin "33") (pinfunction "SD0_33") (pintype "bidirectional"))
    )
    (net (code "157") (name "/SD1") (class "Default")
      (node (ref "U21") (pin "95") (pinfunction "SD1_95") (pintype "bidirectional"))
      (node (ref "U35") (pin "34") (pinfunction "SD1_34") (pintype "bidirectional"))
    )
    (net (code "158") (name "/SD2") (class "Default")
      (node (ref "U21") (pin "94") (pinfunction "SD2_94") (pintype "bidirectional"))
      (node (ref "U35") (pin "35") (pinfunction "SD2_35") (pintype "bidirectional"))
    )
    (net (code "159") (name "/SD3") (class "Default")
      (node (ref "U21") (pin "93") (pinfunction "SD3_93") (pintype "bidirectional"))
      (node (ref "U35") (pin "36") (pinfunction "SD3_36") (pintype "bidirectional"))
    )
    (net (code "160") (name "/SD4") (class "Default")
      (node (ref "U21") (pin "92") (pinfunction "SD4_92") (pintype "bidirectional"))
      (node (ref "U35") (pin "39") (pinfunction "SD4_39") (pintype "bidirectional"))
    )
    (net (code "161") (name "/SD5") (class "Default")
      (node (ref "U21") (pin "91") (pinfunction "SD5_91") (pintype "bidirectional"))
      (node (ref "U35") (pin "40") (pinfunction "SD5_40") (pintype "bidirectional"))
    )
    (net (code "162") (name "/SD6") (class "Default")
      (node (ref "U21") (pin "89") (pinfunction "SD6_89") (pintype "bidirectional"))
      (node (ref "U35") (pin "41") (pinfunction "SD6_41") (pintype "bidirectional"))
    )
    (net (code "163") (name "/SD7") (class "Default")
      (node (ref "U21") (pin "88") (pinfunction "SD7_88") (pintype "bidirectional"))
      (node (ref "U35") (pin "42") (pinfunction "SD7_42") (pintype "bidirectional"))
    )
    (net (code "165") (name "/U21_97") (class "Default")
      (node (ref "U21") (pin "97") (pinfunction "M38_IO1_97") (pintype "bidirectional"))
    )
    (net (code "166") (name "/U21_98") (class "Default")
      (node (ref "U21") (pin "98") (pinfunction "M38_IO2_98") (pintype "bidirectional"))
    )
    (net (code "167") (name "/U21_101") (class "Default")
      (node (ref "U21") (pin "101") (pinfunction "M38_IO3_101") (pintype "bidirectional"))
    )
    (net (code "168") (name "/U21_102") (class "Default")
      (node (ref "U21") (pin "102") (pinfunction "M38_IO4_102") (pintype "bidirectional"))
    )
    (net (code "169") (name "/U21_103") (class "Default")
      (node (ref "U21") (pin "103") (pinfunction "M38_IO5_103") (pintype "bidirectional"))
    )
    (net (code "170") (name "/U21_104") (class "Default")
      (node (ref "U21") (pin "104") (pinfunction "M38_IO6_104") (pintype "bidirectional"))
    )
    (net (code "171") (name "/U21_105") (class "Default")
      (node (ref "U21") (pin "105") (pinfunction "M38_IO7_105") (pintype "bidirectional"))
    )
    (net (code "172") (name "/U21_131") (class "Default")
      (node (ref "U21") (pin "131") (pinfunction "PSU_IO1_131") (pintype "bidirectional"))
    )
    (net (code "173") (name "/U21_139") (class "Default")
      (node (ref "U21") (pin "139") (pinfunction "M38_IO12_139") (pintype "output"))
    )
    (net (code "174") (name "/U30_D0") (class "Default")
      (node (ref "U35") (pin "1") (pinfunction "FF_D0_1") (pintype "input"))
    )
    (net (code "175") (name "/U53_2CLK") (class "Default")
      (node (ref "U35") (pin "3") (pinfunction "FF_2CLK_3") (pintype "output"))
      (node (ref "U40") (pin "11") (pinfunction "C_11") (pintype "input"))
    )
    (net (code "176") (name "/VGA_ADDHI") (class "Default")
      (node (ref "U21") (pin "124") (pinfunction "ADDHI_124") (pintype "output"))
    )
    (net (code "177") (name "/YMF_VSS_Res") (class "Default")
      (node (ref "Q14") (pin "3") (pinfunction "C_3") (pintype "passive"))
      (node (ref "R119") (pin "1") (pinfunction "1_1") (pintype "passive"))
    )
    (net (code "178") (name "GND") (class "Default")
      (node (ref "C108") (pin "1") (pinfunction "+_1") (pintype "passive"))
      (node (ref "C109") (pin "1") (pinfunction "+_1") (pintype "passive"))
      (node (ref "C110") (pin "1") (pinfunction "+_1") (pintype "passive"))
      (node (ref "C111") (pin "2") (pinfunction "2_2") (pintype "passive"))
      (node (ref "C113") (pin "1") (pinfunction "+_1") (pintype "passive"))
      (node (ref "C117") (pin "1") (pinfunction "1_1") (pintype "passive"))
      (node (ref "C121") (pin "2") (pinfunction "2_2") (pintype "passive"))
      (node (ref "C123") (pin "2") (pinfunction "2_2") (pintype "passive"))
      (node (ref "C125") (pin "1") (pinfunction "1_1") (pintype "passive"))
      (node (ref "C127") (pin "1") (pinfunction "1_1") (pintype "passive"))
      (node (ref "C255") (pin "1") (pinfunction "1_1") (pintype "passive"))
      (node (ref "C277") (pin "1") (pinfunction "1_1") (pintype "passive"))
      (node (ref "C280") (pin "1") (pinfunction "1_1") (pintype "passive"))
      (node (ref "C64") (pin "1") (pinfunction "+_1") (pintype "passive"))
      (node (ref "C66") (pin "1") (pinfunction "1_1") (pintype "passive"))
      (node (ref "C71") (pin "1") (pinfunction "1_1") (pintype "passive"))
      (node (ref "C72") (pin "2") (pinfunction "-_2") (pintype "passive"))
      (node (ref "C74") (pin "1") (pinfunction "1_1") (pintype "passive"))
      (node (ref "C78") (pin "1") (pinfunction "1_1") (pintype "passive"))
      (node (ref "Q14") (pin "2") (pinfunction "E_2") (pintype "passive"))
      (node (ref "Q18") (pin "2") (pinfunction "E_2") (pintype "passive"))
      (node (ref "Q19") (pin "2") (pinfunction "E_2") (pintype "passive"))
      (node (ref "Q38") (pin "2") (pinfunction "E_2") (pintype "passive"))
      (node (ref "Q43") (pin "2") (pinfunction "E_2") (pintype "passive"))
      (node (ref "Q44") (pin "2") (pinfunction "E_2") (pintype "passive"))
      (node (ref "R186") (pin "2") (pinfunction "2_2") (pintype "passive"))
      (node (ref "R383") (pin "1") (pinfunction "1_1") (pintype "passive"))
      (node (ref "U21") (pin "100") (pinfunction "GND_100") (pintype "power_in"))
      (node (ref "U21") (pin "116") (pinfunction "GND_116") (pintype "power_in"))
      (node (ref "U21") (pin "136") (pinfunction "GND_136") (pintype "power_in"))
      (node (ref "U21") (pin "28") (pinfunction "GND_28") (pintype "power_in"))
      (node (ref "U21") (pin "44") (pinfunction "GND_44") (pintype "power_in"))
      (node (ref "U21") (pin "64") (pinfunction "GND_64") (pintype "power_in"))
      (node (ref "U21") (pin "8") (pinfunction "GND_8") (pintype "power_in"))
      (node (ref "U21") (pin "80") (pinfunction "GND_80") (pintype "power_in"))
      (node (ref "U35") (pin "13") (pinfunction "GND_13") (pintype "power_in"))
      (node (ref "U35") (pin "37") (pinfunction "GND_37") (pintype "power_in"))
      (node (ref "U35") (pin "4") (pinfunction "GND_4") (pintype "power_in"))
      (node (ref "U35") (pin "63") (pinfunction "GND_63") (pintype "power_in"))
      (node (ref "U35") (pin "87") (pinfunction "GND_87") (pintype "power_in"))
      (node (ref "U37") (pin "3") (pinfunction "GND_3") (pintype "power_in"))
      (node (ref "U38") (pin "4") (pinfunction "GND_4") (pintype "power_in"))
      (node (ref "U39") (pin "4") (pinfunction "GND_4") (pintype "power_in"))
      (node (ref "U40") (pin "7") (pinfunction "GND_7") (pintype "power_in"))
      (node (ref "U45") (pin "8") (pinfunction "GND_8") (pintype "power_in"))
      (node (ref "U45") (pin "9") (pinfunction "A_9") (pintype "input"))
      (node (ref "U9") (pin "3") (pinfunction "GND_3") (pintype "power_in"))
    )
    (net (code "179") (name "Net-(D32-A)") (class "Default")
      (node (ref "D32") (pin "2") (pinfunction "A_2") (pintype "passive"))
      (node (ref "R129") (pin "1") (pinfunction "1_1") (pintype "passive"))
    )
    (net (code "180") (name "Net-(D32-common)") (class "Default")
      (node (ref "D32") (pin "3") (pinfunction "common_3") (pintype "passive"))
      (node (ref "Q18") (pin "1") (pinfunction "B_1") (pintype "input"))
      (node (ref "R180") (pin "1") (pinfunction "1_1") (pintype "passive"))
    )
    (net (code "181") (name "Net-(D33-Pad3)") (class "Default")
      (node (ref "D33") (pin "3") (pinfunction "3_3") (pintype "passive"))
      (node (ref "R114") (pin "2") (pinfunction "2_2") (pintype "passive"))
    )
    (net (code "182") (name "Net-(Q14-B)") (class "Default")
      (node (ref "Q14") (pin "1") (pinfunction "B_1") (pintype "input"))
      (node (ref "R114") (pin "1") (pinfunction "1_1") (pintype "passive"))
    )
    (net (code "183") (name "Net-(Q16-B)") (class "Default")
      (node (ref "Q16") (pin "1") (pinfunction "B_1") (pintype "input"))
      (node (ref "R185") (pin "2") (pinfunction "2_2") (pintype "passive"))
    )
    (net (code "184") (name "Net-(Q18-C)") (class "Default")
      (node (ref "Q18") (pin "3") (pinfunction "C_3") (pintype "passive"))
      (node (ref "R185") (pin "1") (pinfunction "1_1") (pintype "passive"))
    )
    (net (code "185") (name "Net-(Q19-B)") (class "Default")
      (node (ref "Q19") (pin "1") (pinfunction "B_1") (pintype "input"))
      (node (ref "R399") (pin "1") (pinfunction "1_1") (pintype "passive"))
    )
    (net (code "186") (name "Net-(Q19-C)") (class "Default")
      (node (ref "Q19") (pin "3") (pinfunction "C_3") (pintype "passive"))
      (node (ref "R410") (pin "2") (pinfunction "2_2") (pintype "passive"))
    )
    (net (code "187") (name "Net-(Q38-B)") (class "Default")
      (node (ref "C277") (pin "2") (pinfunction "2_2") (pintype "passive"))
      (node (ref "Q38") (pin "1") (pinfunction "B_1") (pintype "input"))
      (node (ref "R382") (pin "2") (pinfunction "2_2") (pintype "passive"))
    )
    (net (code "188") (name "Net-(Q38-C)") (class "Default")
      (node (ref "Q38") (pin "3") (pinfunction "C_3") (pintype "passive"))
      (node (ref "R216") (pin "2") (pinfunction "2_2") (pintype "passive"))
      (node (ref "U35") (pin "45") (pinfunction "FF_1CLK_45") (pintype "output"))
      (node (ref "U38") (pin "1") (pinfunction "1_1") (pintype "input"))
    )
    (net (code "189") (name "Net-(Q43-B)") (class "Default")
      (node (ref "Q43") (pin "1") (pinfunction "B_1") (pintype "input"))
      (node (ref "R392") (pin "1") (pinfunction "1_1") (pintype "passive"))
    )
    (net (code "190") (name "Net-(Q43-C)") (class "Default")
      (node (ref "Q43") (pin "3") (pinfunction "C_3") (pintype "passive"))
      (node (ref "R412") (pin "2") (pinfunction "2_2") (pintype "passive"))
    )
    (net (code "191") (name "Net-(Q44-B)") (class "Default")
      (node (ref "Q44") (pin "1") (pinfunction "B_1") (pintype "input"))
      (node (ref "R398") (pin "1") (pinfunction "1_1") (pintype "passive"))
    )
    (net (code "192") (name "Net-(Q44-C)") (class "Default")
      (node (ref "Q44") (pin "3") (pinfunction "C_3") (pintype "passive"))
      (node (ref "R409") (pin "2") (pinfunction "2_2") (pintype "passive"))
    )
    (net (code "193") (name "Net-(RA1-R1.1)") (class "Default")
      (node (ref "D26") (pin "1") (pinfunction "A_1") (pintype "passive"))
      (node (ref "D26") (pin "3") (pinfunction "A_3") (pintype "passive"))
      (node (ref "RA1") (pin "1") (pinfunction "R1.1_1") (pintype "passive"))
      (node (ref "U35") (pin "69") (pinfunction "FDD_IO2_69") (pintype "bidirectional"))
    )
    (net (code "194") (name "Net-(RA1-R2.1)") (class "Default")
      (node (ref "D28") (pin "1") (pinfunction "A_1") (pintype "passive"))
      (node (ref "D28") (pin "3") (pinfunction "A_3") (pintype "passive"))
      (node (ref "RA1") (pin "2") (pinfunction "R2.1_2") (pintype "passive"))
      (node (ref "U35") (pin "68") (pinfunction "FDD_IO1_68") (pintype "bidirectional"))
    )
    (net (code "195") (name "Net-(RA1-R3.1)") (class "Default")
      (node (ref "D27") (pin "1") (pinfunction "A_1") (pintype "passive"))
      (node (ref "D27") (pin "3") (pinfunction "A_3") (pintype "passive"))
      (node (ref "RA1") (pin "3") (pinfunction "R3.1_3") (pintype "passive"))
      (node (ref "U35") (pin "71") (pinfunction "FDD_IO4_71") (pintype "bidirectional"))
    )
    (net (code "196") (name "Net-(RA1-R4.1)") (class "Default")
      (node (ref "D29") (pin "1") (pinfunction "A_1") (pintype "passive"))
      (node (ref "D29") (pin "3") (pinfunction "A_3") (pintype "passive"))
      (node (ref "RA1") (pin "4") (pinfunction "R4.1_4") (pintype "passive"))
      (node (ref "U35") (pin "70") (pinfunction "FDD_IO3_70") (pintype "bidirectional"))
    )
    (net (code "197") (name "Net-(SW2-B)") (class "Default")
      (node (ref "R382") (pin "1") (pinfunction "1_1") (pintype "passive"))
      (node (ref "R383") (pin "2") (pinfunction "2_2") (pintype "passive"))
      (node (ref "SW2") (pin "2") (pinfunction "B_2") (pintype "passive"))
    )
    (net (code "198") (name "Net-(U21-CPUCLK)") (class "Default")
      (node (ref "R257") (pin "1") (pinfunction "1_1") (pintype "passive"))
      (node (ref "U21") (pin "38") (pinfunction "CPUCLK_38") (pintype "input"))
    )
    (net (code "199") (name "Net-(U21-Chipset_IO3)") (class "Default")
      (node (ref "R149") (pin "1") (pinfunction "1_1") (pintype "passive"))
      (node (ref "U21") (pin "39") (pinfunction "Chipset_IO3_39") (pintype "bidirectional"))
    )
    (net (code "200") (name "Net-(U21-PSU_IO2)") (class "Default")
      (node (ref "R104") (pin "1") (pinfunction "1_1") (pintype "passive"))
      (node (ref "U21") (pin "138") (pinfunction "PSU_IO2_138") (pintype "bidirectional"))
    )
    (net (code "201") (name "Net-(U21-PWRGD_IN)") (class "Default")
      (node (ref "U21") (pin "141") (pinfunction "PWRGD_IN_141") (pintype "input"))
      (node (ref "U9") (pin "4") (pinfunction "4_4") (pintype "output"))
    )
    (net (code "202") (name "Net-(U35-FF_2D)") (class "Default")
      (node (ref "R186") (pin "1") (pinfunction "1_1") (pintype "passive"))
      (node (ref "U35") (pin "2") (pinfunction "FF_2D_2") (pintype "output"))
      (node (ref "U40") (pin "12") (pinfunction "D_12") (pintype "input"))
    )
    (net (code "203") (name "Net-(U35-FF_2Q#)") (class "Default")
      (node (ref "U35") (pin "90") (pinfunction "FF_2Q#_90") (pintype "input"))
      (node (ref "U40") (pin "1") (pinfunction "~{{R}}_1") (pintype "input"))
      (node (ref "U45") (pin "12") (pinfunction "~{{Q}}_12") (pintype "output"))
    )
    (net (code "204") (name "Net-(U35-PNET7_SENSE)") (class "Default")
      (node (ref "R304") (pin "1") (pinfunction "1_1") (pintype "passive"))
      (node (ref "U35") (pin "74") (pinfunction "PNET7_SENSE_74") (pintype "input"))
    )
    (net (code "205") (name "Net-(U35-Pluto_55)") (class "Default")
      (node (ref "R398") (pin "2") (pinfunction "2_2") (pintype "passive"))
      (node (ref "U35") (pin "55") (pinfunction "Pluto_55_55") (pintype "input"))
    )
    (net (code "206") (name "Net-(U35-Pluto_56)") (class "Default")
      (node (ref "R392") (pin "2") (pinfunction "2_2") (pintype "passive"))
      (node (ref "U35") (pin "56") (pinfunction "Pluto_56_56") (pintype "input"))
    )
    (net (code "207") (name "Net-(U35-Pluto_57)") (class "Default")
      (node (ref "R399") (pin "2") (pinfunction "2_2") (pintype "passive"))
      (node (ref "U35") (pin "57") (pinfunction "Pluto_57_57") (pintype "input"))
    )
    (net (code "208") (name "Net-(U35-SA13)") (class "Default")
      (node (ref "U35") (pin "23") (pinfunction "SA13_23") (pintype "input"))
      (node (ref "U37") (pin "4") (pinfunction "4_4") (pintype "output"))
    )
    (net (code "209") (name "Net-(U38-Pad5)") (class "Default")
      (node (ref "U38") (pin "5") (pinfunction "5_5") (pintype "output"))
      (node (ref "U9") (pin "2") (pinfunction "2_2") (pintype "input"))
    )
    (net (code "210") (name "Net-(U40A-C)") (class "Default")
      (node (ref "U38") (pin "7") (pinfunction "7_7") (pintype "output"))
      (node (ref "U39") (pin "2") (pinfunction "2_2") (pintype "input"))
      (node (ref "U40") (pin "3") (pinfunction "C_3") (pintype "input"))
    )
    (net (code "211") (name "Net-(U40A-~{{Q}})") (class "Default")
      (node (ref "C125") (pin "2") (pinfunction "2_2") (pintype "passive"))
      (node (ref "U39") (pin "1") (pinfunction "1_1") (pintype "input"))
      (node (ref "U40") (pin "6") (pinfunction "~{{Q}}_6") (pintype "output"))
    )
    (net (code "212") (name "Net-(U40B-~{{Q}})") (class "Default")
      (node (ref "U40") (pin "8") (pinfunction "~{{Q}}_8") (pintype "output"))
      (node (ref "U45") (pin "11") (pinfunction "Clr_11") (pintype "input"))
    )
    (net (code "213") (name "Net-(U45A-A)") (class "Default")
      (node (ref "U35") (pin "46") (pinfunction "FF_1A_46") (pintype "output"))
      (node (ref "U35") (pin "78") (pinfunction "FF_1A_78") (pintype "input"))
      (node (ref "U45") (pin "1") (pinfunction "A_1") (pintype "input"))
    )
    (net (code "214") (name "Net-(U45A-Cext)") (class "Default")
      (node (ref "C130") (pin "2") (pinfunction "2_2") (pintype "passive"))
      (node (ref "U45") (pin "14") (pinfunction "Cext_14") (pintype "input"))
    )
    (net (code "215") (name "Net-(U45A-Q)") (class "Default")
      (node (ref "D33") (pin "2") (pinfunction "2_2") (pintype "passive"))
      (node (ref "U45") (pin "13") (pinfunction "Q_13") (pintype "output"))
    )
    (net (code "216") (name "Net-(U45A-RCext)") (class "Default")
      (node (ref "C130") (pin "1") (pinfunction "1_1") (pintype "passive"))
      (node (ref "R182") (pin "2") (pinfunction "2_2") (pintype "passive"))
      (node (ref "U45") (pin "15") (pinfunction "RCext_15") (pintype "input"))
    )
    (net (code "217") (name "Net-(U45B-B)") (class "Default")
      (node (ref "U39") (pin "7") (pinfunction "7_7") (pintype "output"))
      (node (ref "U45") (pin "10") (pinfunction "B_10") (pintype "input"))
    )
    (net (code "218") (name "Net-(U45B-Q)") (class "Default")
      (node (ref "D33") (pin "1") (pinfunction "1_1") (pintype "passive"))
      (node (ref "U45") (pin "5") (pinfunction "Q_5") (pintype "output"))
    )
    (net (code "219") (name "Net-(U45B-RCext)") (class "Default")
      (node (ref "C140") (pin "1") (pinfunction "1_1") (pintype "passive"))
      (node (ref "R215") (pin "1") (pinfunction "1_1") (pintype "passive"))
      (node (ref "U45") (pin "7") (pinfunction "RCext_7") (pintype "input"))
    )
    (net (code "220") (name "PNET1") (class "Default")
      (node (ref "C108") (pin "2") (pinfunction "-_2") (pintype "passive"))
      (node (ref "C109") (pin "2") (pinfunction "-_2") (pintype "passive"))
      (node (ref "C110") (pin "2") (pinfunction "-_2") (pintype "passive"))
      (node (ref "C111") (pin "1") (pinfunction "1_1") (pintype "passive"))
      (node (ref "C113") (pin "2") (pinfunction "-_2") (pintype "passive"))
      (node (ref "C117") (pin "2") (pinfunction "2_2") (pintype "passive"))
      (node (ref "C121") (pin "1") (pinfunction "1_1") (pintype "passive"))
      (node (ref "C123") (pin "1") (pinfunction "1_1") (pintype "passive"))
      (node (ref "C127") (pin "2") (pinfunction "2_2") (pintype "passive"))
      (node (ref "C140") (pin "2") (pinfunction "2_2") (pintype "passive"))
      (node (ref "C255") (pin "2") (pinfunction "2_2") (pintype "passive"))
      (node (ref "C280") (pin "2") (pinfunction "2_2") (pintype "passive"))
      (node (ref "C64") (pin "2") (pinfunction "-_2") (pintype "passive"))
      (node (ref "C71") (pin "2") (pinfunction "2_2") (pintype "passive"))
      (node (ref "C72") (pin "1") (pinfunction "+_1") (pintype "passive"))
      (node (ref "C74") (pin "2") (pinfunction "2_2") (pintype "passive"))
      (node (ref "C78") (pin "2") (pinfunction "2_2") (pintype "passive"))
      (node (ref "R182") (pin "1") (pinfunction "1_1") (pintype "passive"))
      (node (ref "R215") (pin "2") (pinfunction "2_2") (pintype "passive"))
      (node (ref "R216") (pin "1") (pinfunction "1_1") (pintype "passive"))
      (node (ref "R393") (pin "1") (pinfunction "1_1") (pintype "passive"))
      (node (ref "SW2") (pin "1") (pinfunction "A_1") (pintype "passive"))
      (node (ref "U21") (pin "1") (pinfunction "VCC_1") (pintype "power_in"))
      (node (ref "U21") (pin "108") (pinfunction "VCC_108") (pintype "power_in"))
      (node (ref "U21") (pin "109") (pinfunction "VCC_109") (pintype "power_in"))
      (node (ref "U21") (pin "126") (pinfunction "VCC_126") (pintype "power_in"))
      (node (ref "U21") (pin "144") (pinfunction "VCC_144") (pintype "power_in"))
      (node (ref "U21") (pin "18") (pinfunction "VCC_18") (pintype "power_in"))
      (node (ref "U21") (pin "36") (pinfunction "VCC_36") (pintype "power_in"))
      (node (ref "U21") (pin "37") (pinfunction "VCC_37") (pintype "power_in"))
      (node (ref "U21") (pin "54") (pinfunction "VCC_54") (pintype "power_in"))
      (node (ref "U21") (pin "72") (pinfunction "VCC_72") (pintype "power_in"))
      (node (ref "U21") (pin "73") (pinfunction "VCC_73") (pintype "power_in"))
      (node (ref "U21") (pin "90") (pinfunction "VCC_90") (pintype "power_in"))
      (node (ref "U35") (pin "14") (pinfunction "VCC_14") (pintype "power_in"))
      (node (ref "U35") (pin "38") (pinfunction "VCC_38") (pintype "power_in"))
      (node (ref "U35") (pin "64") (pinfunction "VCC_64") (pintype "power_in"))
      (node (ref "U35") (pin "7") (pinfunction "VCC_7") (pintype "power_in"))
      (node (ref "U35") (pin "88") (pinfunction "VCC_88") (pintype "power_in"))
      (node (ref "U35") (pin "95") (pinfunction "VCC_95") (pintype "power_in"))
      (node (ref "U35") (pin "97") (pinfunction "VCC_97") (pintype "power_in"))
      (node (ref "U37") (pin "5") (pinfunction "VCC_5") (pintype "power_in"))
      (node (ref "U38") (pin "8") (pinfunction "VCC_8") (pintype "power_in"))
      (node (ref "U39") (pin "8") (pinfunction "VCC_8") (pintype "power_in"))
      (node (ref "U40") (pin "13") (pinfunction "~{{R}}_13") (pintype "input"))
      (node (ref "U40") (pin "14") (pinfunction "VCC_14") (pintype "power_in"))
      (node (ref "U40") (pin "2") (pinfunction "D_2") (pintype "input"))
      (node (ref "U45") (pin "16") (pinfunction "VCC_16") (pintype "power_in"))
      (node (ref "U45") (pin "2") (pinfunction "B_2") (pintype "input"))
      (node (ref "U45") (pin "6") (pinfunction "Cext_6") (pintype "input"))
      (node (ref "U9") (pin "5") (pinfunction "VCC_5") (pintype "power_in"))
    )
    (net (code "221") (name "PNET2") (class "Default")
      (node (ref "U21") (pin "99") (pinfunction "VCC2_99") (pintype "power_in"))
    )
    (net (code "222") (name "PNET5") (class "Default")
      (node (ref "Q16") (pin "2") (pinfunction "E_2") (pintype "passive"))
    )
    (net (code "223") (name "PNET7") (class "Default")
      (node (ref "R304") (pin "2") (pinfunction "2_2") (pintype "passive"))
      (node (ref "RA1") (pin "5") (pinfunction "R4.2_5") (pintype "passive"))
      (node (ref "RA1") (pin "6") (pinfunction "R3.2_6") (pintype "passive"))
      (node (ref "RA1") (pin "7") (pinfunction "R2.2_7") (pintype "passive"))
      (node (ref "RA1") (pin "8") (pinfunction "R1.2_8") (pintype "passive"))
    )
    (net (code "224") (name "unconnected-(U21-NC-Pad132)") (class "Default")
      (node (ref "U21") (pin "132") (pinfunction "NC_132") (pintype "input"))
    )
    (net (code "225") (name "unconnected-(U21-NC-Pad135)") (class "Default")
      (node (ref "U21") (pin "135") (pinfunction "NC_135") (pintype "input"))
    )
    (net (code "226") (name "unconnected-(U21-NC-Pad137)") (class "Default")
      (node (ref "U21") (pin "137") (pinfunction "NC_137") (pintype "input"))
    )
    (net (code "227") (name "unconnected-(U35-NC-Pad47)") (class "Default")
      (node (ref "U35") (pin "47") (pinfunction "NC_47") (pintype "input"))
    )
    (net (code "228") (name "unconnected-(U35-NC-Pad49)") (class "Default")
      (node (ref "U35") (pin "49") (pinfunction "NC_49") (pintype "input"))
    )
    (net (code "229") (name "unconnected-(U35-NC-Pad59)") (class "Default")
      (node (ref "U35") (pin "59") (pinfunction "NC_59") (pintype "input"))
    )
    (net (code "230") (name "unconnected-(U35-NC-Pad80)") (class "Default")
      (node (ref "U35") (pin "80") (pinfunction "NC_80") (pintype "input"))
    )
    (net (code "231") (name "unconnected-(U35-NC-Pad82)") (class "Default")
      (node (ref "U35") (pin "82") (pinfunction "NC_82") (pintype "input"))
    )
    (net (code "232") (name "unconnected-(U35-NC-Pad84)") (class "Default")
      (node (ref "U35") (pin "84") (pinfunction "NC_84") (pintype "input"))
    )
    (net (code "233") (name "unconnected-(U35-NC-Pad85)") (class "Default")
      (node (ref "U35") (pin "85") (pinfunction "NC_85") (pintype "input"))
    )
    (net (code "234") (name "unconnected-(U35-NC-Pad91)") (class "Default")
      (node (ref "U35") (pin "91") (pinfunction "NC_91") (pintype "input"))
    )
    (net (code "235") (name "unconnected-(U35-NC-Pad92)") (class "Default")
      (node (ref "U35") (pin "92") (pinfunction "NC_92") (pintype "input"))
    )
    (net (code "236") (name "unconnected-(U35-NC-Pad94)") (class "Default")
      (node (ref "U35") (pin "94") (pinfunction "NC_94") (pintype "input"))
    )
    (net (code "237") (name "unconnected-(U35-NC-Pad96)") (class "Default")
      (node (ref "U35") (pin "96") (pinfunction "NC_96") (pintype "input"))
    )
    (net (code "238") (name "unconnected-(U35-NC-Pad98)") (class "Default")
      (node (ref "U35") (pin "98") (pinfunction "NC_98") (pintype "input"))
    )
    (net (code "239") (name "unconnected-(U35-NC-Pad99)") (class "Default")
      (node (ref "U35") (pin "99") (pinfunction "NC_99") (pintype "input"))
    )
    (net (code "240") (name "unconnected-(U35-NC-Pad100)") (class "Default")
      (node (ref "U35") (pin "100") (pinfunction "NC_100") (pintype "input"))
    )
    (net (code "241") (name "unconnected-(U40A-Q-Pad5)") (class "Default")
      (node (ref "U40") (pin "5") (pinfunction "Q_5") (pintype "output+no_connect"))
    )
    (net (code "242") (name "unconnected-(U40B-Q-Pad9)") (class "Default")
      (node (ref "U40") (pin "9") (pinfunction "Q_9") (pintype "output+no_connect"))
    )
    (net (code "243") (name "unconnected-(U45A-~{{Q}}-Pad4)") (class "Default")
      (node (ref "U45") (pin "4") (pinfunction "~{{Q}}_4") (pintype "output+no_connect"))
    )
  )
)
